# USB.net
KiCad netlist of a schematic drawn in Altium Designer
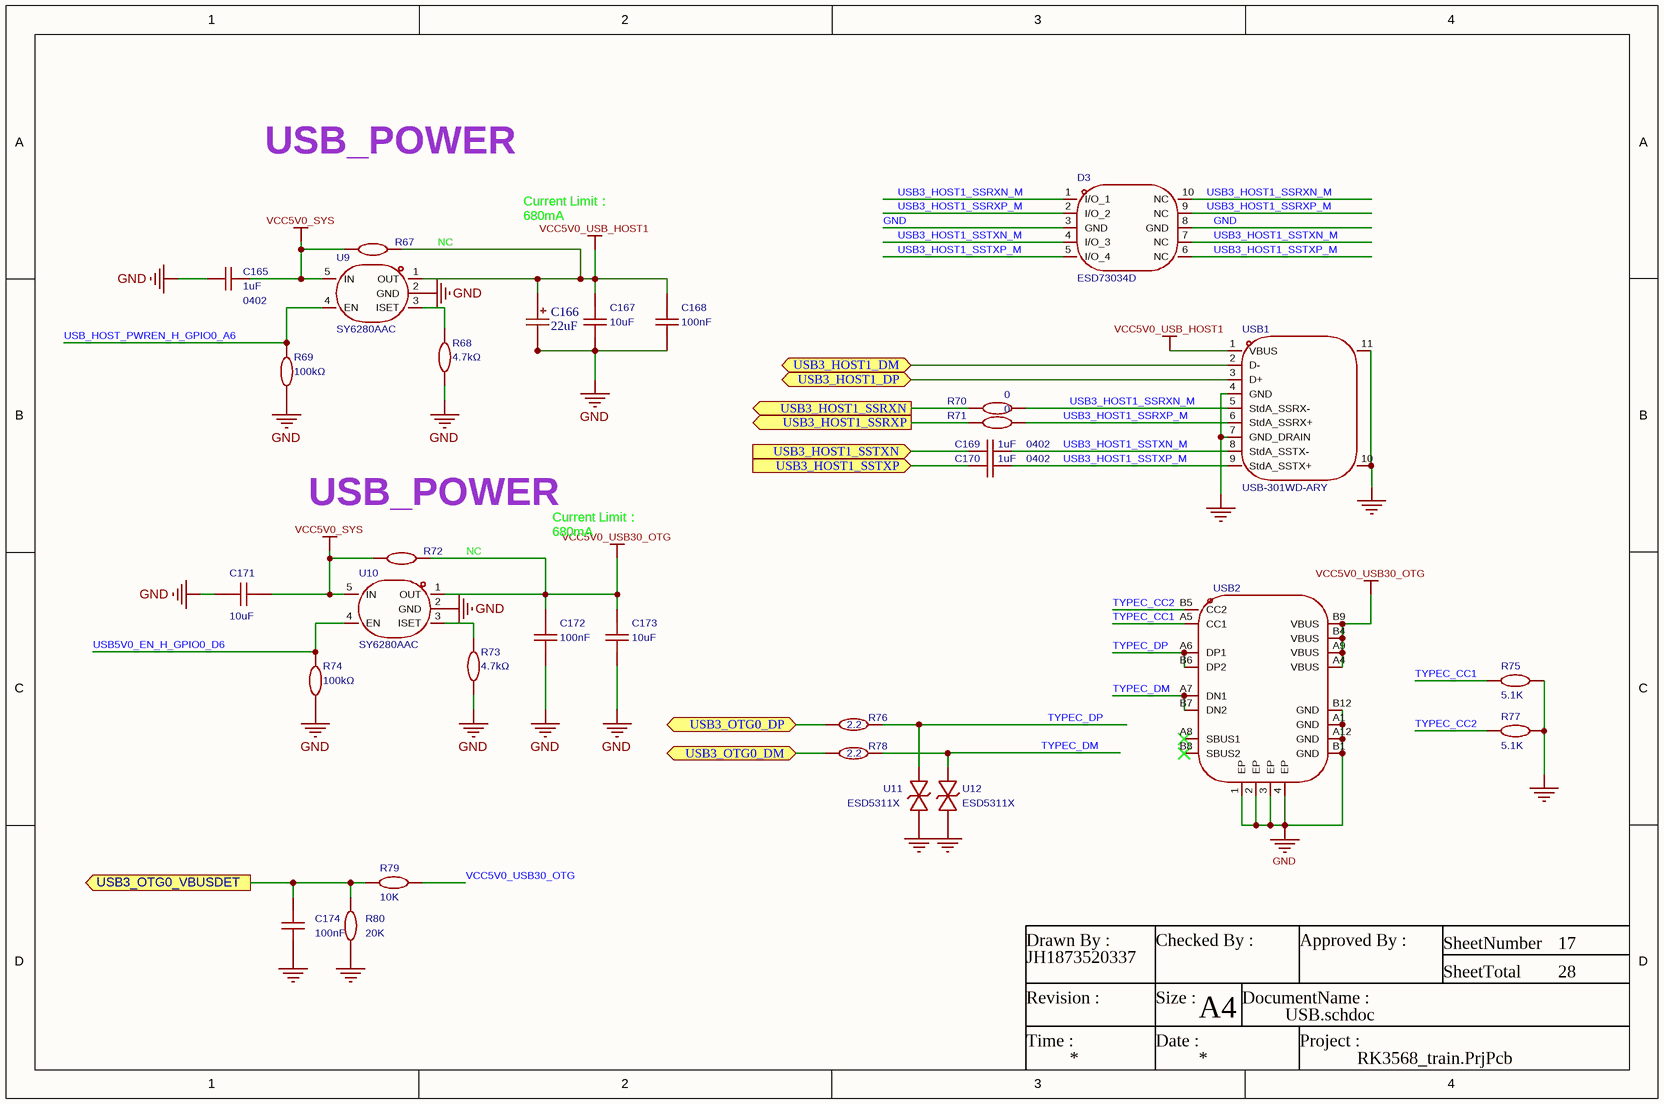
[diagram p0: USB.schdoc]

(export (version "E")
  (design (tool "Eeschema 10.0.6"))
  (components
    (comp (ref "C165")
      (value "1uF")
      (footprint "MYC0402")
      (description "容值:1uF;精度:±10%;额定电压:10V;材质(温度系数):X5R;")
      (fields
        (field (name "SUPPLIER FOOTPRINT") "0402")
        (field (name "MANUFACTURER") "SAMSUNG(三星)")
        (field (name "MANUFACTURER PART") "CL05A105KP5NNNC")
      )
      (libsource (lib "altium-import") (part "root_0_CL05A105KP5NNNC_"))
    )
    (comp (ref "C166")
      (value "22uF")
      (footprint "CASE-B_3528")
      (description "容值:22uF;精度:±10%;额定电压:16V;等效串联电阻(ESR):2.3Ω@100kHz;")
      (fields (field (name "MANUFACTURER") "Kyocera AVX") (field (name "MANUFACTURER PART") "TAJB226K016RNJ"))
      (libsource (lib "钽电容") (part "TAJB226K016RNJ"))
    )
    (comp (ref "C167")
      (value "10uF")
      (footprint "C0603")
      (description "容值:10uF;精度:±10%;额定电压:10V;材质(温度系数):X5R;")
      (fields (field (name "MANUFACTURER") "SAMSUNG(三星)") (field (name "MANUFACTURERPART") "CL10A106KP8NNNC"))
      (libsource (lib "altium-import") (part "root_1_CL10A106KP8NNNC_"))
    )
    (comp (ref "C168")
      (value "100nF")
      (footprint "C0603")
      (description "容值:100nF;精度:±10%;额定电压:50V;材质(温度系数):X7R;")
      (fields (field (name "MANUFACTURER") "YAGEO(国巨)") (field (name "MANUFACTURERPART") "CC0603KRX7R9BB104"))
      (libsource (lib "altium-import") (part "root_1_CC0603KRX7R9BB104_"))
    )
    (comp (ref "C169")
      (value "1uF")
      (footprint "MYC0402")
      (description "容值:1uF;精度:±10%;额定电压:10V;材质(温度系数):X5R;")
      (fields
        (field (name "SUPPLIER FOOTPRINT") "0402")
        (field (name "MANUFACTURER") "SAMSUNG(三星)")
        (field (name "MANUFACTURERPART") "CL05A105KP5NNNC")
      )
      (libsource (lib "altium-import") (part "root_0_CL05A105KP5NNNC_"))
    )
    (comp (ref "C170")
      (value "1uF")
      (footprint "MYC0402")
      (description "容值:1uF;精度:±10%;额定电压:10V;材质(温度系数):X5R;")
      (fields
        (field (name "SUPPLIER FOOTPRINT") "0402")
        (field (name "MANUFACTURER") "SAMSUNG(三星)")
        (field (name "MANUFACTURERPART") "CL05A105KP5NNNC")
      )
      (libsource (lib "altium-import") (part "root_0_CL05A105KP5NNNC_"))
    )
    (comp (ref "C171")
      (value "10uF")
      (footprint "C0603")
      (libsource (lib "altium-import") (part "root_0_CAP_0603_"))
    )
    (comp (ref "C172")
      (value "100nF")
      (footprint "C0603")
      (description "容值:100nF;精度:±10%;额定电压:50V;材质(温度系数):X7R;")
      (fields (field (name "MANUFACTURER") "YAGEO(国巨)") (field (name "MANUFACTURERPART") "CC0603KRX7R9BB104"))
      (libsource (lib "altium-import") (part "root_1_CC0603KRX7R9BB104_"))
    )
    (comp (ref "C173")
      (value "10uF")
      (footprint "C0603")
      (description "容值:10uF;精度:±10%;额定电压:10V;材质(温度系数):X5R;")
      (fields (field (name "MANUFACTURER") "SAMSUNG(三星)") (field (name "MANUFACTURERPART") "CL10A106KP8NNNC"))
      (libsource (lib "altium-import") (part "root_1_CL10A106KP8NNNC_"))
    )
    (comp (ref "C174")
      (value "100nF")
      (footprint "MYC0402")
      (description "容值:1uF;精度:±10%;额定电压:50V;材质(温度系数):X5R;")
      (fields (field (name "MANUFACTURER") "SAMSUNG(三星)") (field (name "MANUFACTURERPART") "CL10A105KB8NNNC"))
      (libsource (lib "altium-import") (part "root_3_CL10A105KB8NNNC_"))
    )
    (comp (ref "D3")
      (value "ESD73034D")
      (footprint "DFN-10_L2.5-W1.0-P0.50-BL-2")
      (description "极性:双向;反向截止电压(Vrwm):3.3V;钳位电压:18V;峰值脉冲电流(Ipp):3A@8/20us;峰值脉冲功率(Ppp):60W@8/20us;击穿电压:8.5V;")
      (fields (field (name "MANUFACTURER") "TECH PUBLIC(台舟)"))
      (libsource (lib "altium-import") (part "root_0_ESD73034D_"))
    )
    (comp (ref "R67")
      (value "NC")
      (footprint "R0805")
      (description "电阻类型:厚膜电阻;阻值:0Ω;精度:±1%;功率:125mW;温度系数:±800ppm/℃;最大工作电压:150V;工作温度范围:-55℃~+155℃;")
      (fields
        (field (name "MANUFACTURER") "UNI-ROYAL(厚声)")
        (field (name "MANUFACTURERPART") "0805W8F0000T5E")
      )
      (libsource (lib "altium-import") (part "root_0_0805W8F0000T5E_"))
    )
    (comp (ref "R68")
      (value "4.7kΩ")
      (footprint "R0402")
      (description "电阻类型:厚膜电阻;阻值:10kΩ;精度:±1%;功率:63mW;温度系数:±100ppm/K;最大工作电压:50V;工作温度范围:-55℃~+155℃;")
      (fields (field (name "MANUFACTURER") "VISHAY(威世)") (field (name "MANUFACTURERPART") "CRCW040210K0FKED"))
      (libsource (lib "altium-import") (part "root_1_CRCW040210K0FKED_"))
    )
    (comp (ref "R69")
      (value "100kΩ")
      (footprint "R0402")
      (description "电阻类型:厚膜电阻;阻值:10kΩ;精度:±1%;功率:63mW;温度系数:±100ppm/K;最大工作电压:50V;工作温度范围:-55℃~+155℃;")
      (fields (field (name "MANUFACTURER") "VISHAY(威世)") (field (name "MANUFACTURERPART") "CRCW040210K0FKED"))
      (libsource (lib "altium-import") (part "root_1_CRCW040210K0FKED_"))
    )
    (comp (ref "R70")
      (value "0")
      (footprint "R0402")
      (libsource (lib "altium-import") (part "root_0_Res_0402_"))
    )
    (comp (ref "R71")
      (value "0")
      (footprint "R0402")
      (libsource (lib "altium-import") (part "root_0_Res_0402_"))
    )
    (comp (ref "R72")
      (value "NC")
      (footprint "R0805")
      (description "电阻类型:厚膜电阻;阻值:0Ω;精度:±1%;功率:125mW;温度系数:±800ppm/℃;最大工作电压:150V;工作温度范围:-55℃~+155℃;")
      (fields
        (field (name "MANUFACTURER") "UNI-ROYAL(厚声)")
        (field (name "MANUFACTURERPART") "0805W8F0000T5E")
      )
      (libsource (lib "altium-import") (part "root_0_0805W8F0000T5E_"))
    )
    (comp (ref "R73")
      (value "4.7kΩ")
      (footprint "R0402")
      (description "电阻类型:厚膜电阻;阻值:10kΩ;精度:±1%;功率:63mW;温度系数:±100ppm/K;最大工作电压:50V;工作温度范围:-55℃~+155℃;")
      (fields (field (name "MANUFACTURER") "VISHAY(威世)") (field (name "MANUFACTURERPART") "CRCW040210K0FKED"))
      (libsource (lib "altium-import") (part "root_1_CRCW040210K0FKED_"))
    )
    (comp (ref "R74")
      (value "100kΩ")
      (footprint "R0402")
      (description "电阻类型:厚膜电阻;阻值:10kΩ;精度:±1%;功率:63mW;温度系数:±100ppm/K;最大工作电压:50V;工作温度范围:-55℃~+155℃;")
      (fields (field (name "MANUFACTURER") "VISHAY(威世)") (field (name "MANUFACTURERPART") "CRCW040210K0FKED"))
      (libsource (lib "altium-import") (part "root_1_CRCW040210K0FKED_"))
    )
    (comp (ref "R75")
      (value "5.1K")
      (footprint "R0402")
      (libsource (lib "altium-import") (part "root_2_Res_0402_"))
    )
    (comp (ref "R76")
      (value "2.2")
      (footprint "R0402")
      (libsource (lib "altium-import") (part "root_0_Res_0402_"))
    )
    (comp (ref "R77")
      (value "5.1K")
      (footprint "R0402")
      (libsource (lib "altium-import") (part "root_2_Res_0402_"))
    )
    (comp (ref "R78")
      (value "2.2")
      (footprint "R0402")
      (libsource (lib "altium-import") (part "root_0_Res_0402_"))
    )
    (comp (ref "R79")
      (value "10K")
      (footprint "R0402")
      (libsource (lib "altium-import") (part "root_0_Res_0402_"))
    )
    (comp (ref "R80")
      (value "20K")
      (footprint "R0402")
      (libsource (lib "altium-import") (part "root_1_Res_0402_"))
    )
    (comp (ref "U9")
      (value "SY6280AAC")
      (footprint "SOT-23-5_L3.0-W1.7-P0.95-LS2.8-BL")
      (description "低能耗配电开关")
      (fields (field (name "MANUFACTURER") "silergy(矽力杰)"))
      (libsource (lib "altium-import") (part "root_3_mirrored_SY6280AAC_C55136_"))
    )
    (comp (ref "U10")
      (value "SY6280AAC")
      (footprint "SOT-23-5_L3.0-W1.7-P0.95-LS2.8-BL")
      (description "低能耗配电开关")
      (fields (field (name "MANUFACTURER") "silergy(矽力杰)"))
      (libsource (lib "altium-import") (part "root_3_mirrored_SY6280AAC_C55136_"))
    )
    (comp (ref "U11")
      (value "ESD5311X")
      (footprint "DFN1006-2L-BI")
      (description "极性:双向;反向截止电压(Vrwm):5V;最大钳位电压:21V;峰值脉冲电流(Ipp):4A;峰值脉冲功率(Ppp):80W;击穿电压:7.5V;")
      (fields (field (name "MANUFACTURER") "TECH PUBLIC(台舟)"))
      (libsource (lib "altium-import") (part "root_3_ESD5311X_C2844730_"))
    )
    (comp (ref "U12")
      (value "ESD5311X")
      (footprint "DFN1006-2L-BI")
      (description "极性:双向;反向截止电压(Vrwm):5V;最大钳位电压:21V;峰值脉冲电流(Ipp):4A;峰值脉冲功率(Ppp):80W;击穿电压:7.5V;")
      (fields (field (name "MANUFACTURER") "TECH PUBLIC(台舟)"))
      (libsource (lib "altium-import") (part "root_3_ESD5311X_C2844730_"))
    )
    (comp (ref "USB1")
      (value "USB-301WD-ARY")
      (footprint "USB-TH_XUNPU_USB-301WD-ARY")
      (description "连接器类型:Type-A;协议标准:USB 3.0;公母:母;安装方式:弯插;触点数量:9P;端口数量:1;额定电流 - 电源:1.8A;工作温度:-55℃~+85℃;")
      (fields (field (name "MANUFACTURER") "XUNPU(讯普)"))
      (libsource (lib "altium-import") (part "root_0_USB-301WD-ARY_"))
    )
    (comp (ref "USB2")
      (value "~")
      (footprint "USB_TYPE-C-16P")
      (libsource (lib "altium-import") (part "root_0_USB_TYPE-C-16P_"))
    )
  )
  (nets
    (net (code "1") (name "/TYPEC_CC1") (class "Default")
      (node (ref "R75") (pin "2") (pinfunction "2_2") (pintype "passive"))
      (node (ref "USB2") (pin "A5") (pinfunction "CC1_A5") (pintype "passive"))
    )
    (net (code "2") (name "/TYPEC_CC2") (class "Default")
      (node (ref "R77") (pin "2") (pinfunction "2_2") (pintype "passive"))
      (node (ref "USB2") (pin "B5") (pinfunction "CC2_B5") (pintype "passive"))
    )
    (net (code "3") (name "/TYPEC_DM") (class "Default")
      (node (ref "R78") (pin "2") (pinfunction "2_2") (pintype "passive"))
      (node (ref "U12") (pin "1") (pinfunction "1_1") (pintype "passive"))
      (node (ref "USB2") (pin "A7") (pinfunction "DN1_A7") (pintype "passive"))
      (node (ref "USB2") (pin "B7") (pinfunction "DN2_B7") (pintype "passive"))
    )
    (net (code "4") (name "/TYPEC_DP") (class "Default")
      (node (ref "R76") (pin "2") (pinfunction "2_2") (pintype "passive"))
      (node (ref "U11") (pin "1") (pinfunction "1_1") (pintype "passive"))
      (node (ref "USB2") (pin "A6") (pinfunction "DP1_A6") (pintype "passive"))
      (node (ref "USB2") (pin "B6") (pinfunction "DP2_B6") (pintype "passive"))
    )
    (net (code "5") (name "/USB3_HOST1_DM") (class "Default")
      (node (ref "USB1") (pin "2") (pinfunction "D-_2") (pintype "passive"))
    )
    (net (code "6") (name "/USB3_HOST1_DP") (class "Default")
      (node (ref "USB1") (pin "3") (pinfunction "D+_3") (pintype "passive"))
    )
    (net (code "7") (name "/USB3_HOST1_SSRXN") (class "Default")
      (node (ref "R70") (pin "1") (pinfunction "1_1") (pintype "passive"))
    )
    (net (code "8") (name "/USB3_HOST1_SSRXN_M") (class "Default")
      (node (ref "D3") (pin "1") (pinfunction "I/O_1_1") (pintype "passive"))
      (node (ref "D3") (pin "10") (pinfunction "NC_10") (pintype "passive"))
      (node (ref "R70") (pin "2") (pinfunction "2_2") (pintype "passive"))
      (node (ref "USB1") (pin "5") (pinfunction "StdA_SSRX-_5") (pintype "passive"))
    )
    (net (code "9") (name "/USB3_HOST1_SSRXP") (class "Default")
      (node (ref "R71") (pin "1") (pinfunction "1_1") (pintype "passive"))
    )
    (net (code "10") (name "/USB3_HOST1_SSRXP_M") (class "Default")
      (node (ref "D3") (pin "2") (pinfunction "I/O_2_2") (pintype "passive"))
      (node (ref "D3") (pin "9") (pinfunction "NC_9") (pintype "passive"))
      (node (ref "R71") (pin "2") (pinfunction "2_2") (pintype "passive"))
      (node (ref "USB1") (pin "6") (pinfunction "StdA_SSRX+_6") (pintype "passive"))
    )
    (net (code "11") (name "/USB3_HOST1_SSTXN") (class "Default")
      (node (ref "C169") (pin "1") (pinfunction "1_1") (pintype "passive"))
    )
    (net (code "12") (name "/USB3_HOST1_SSTXN_M") (class "Default")
      (node (ref "C169") (pin "2") (pinfunction "2_2") (pintype "passive"))
      (node (ref "D3") (pin "4") (pinfunction "I/O_3_4") (pintype "passive"))
      (node (ref "D3") (pin "7") (pinfunction "NC_7") (pintype "passive"))
      (node (ref "USB1") (pin "8") (pinfunction "StdA_SSTX-_8") (pintype "passive"))
    )
    (net (code "13") (name "/USB3_HOST1_SSTXP") (class "Default")
      (node (ref "C170") (pin "1") (pinfunction "1_1") (pintype "passive"))
    )
    (net (code "14") (name "/USB3_HOST1_SSTXP_M") (class "Default")
      (node (ref "C170") (pin "2") (pinfunction "2_2") (pintype "passive"))
      (node (ref "D3") (pin "5") (pinfunction "I/O_4_5") (pintype "passive"))
      (node (ref "D3") (pin "6") (pinfunction "NC_6") (pintype "passive"))
      (node (ref "USB1") (pin "9") (pinfunction "StdA_SSTX+_9") (pintype "passive"))
    )
    (net (code "15") (name "/USB3_OTG0_DM") (class "Default")
      (node (ref "R78") (pin "1") (pinfunction "1_1") (pintype "passive"))
    )
    (net (code "16") (name "/USB3_OTG0_DP") (class "Default")
      (node (ref "R76") (pin "1") (pinfunction "1_1") (pintype "passive"))
    )
    (net (code "17") (name "/USB3_OTG0_VBUSDET") (class "Default")
      (node (ref "C174") (pin "1") (pinfunction "1_1") (pintype "passive"))
      (node (ref "R79") (pin "1") (pinfunction "1_1") (pintype "passive"))
      (node (ref "R80") (pin "2") (pinfunction "2_2") (pintype "passive"))
    )
    (net (code "18") (name "/USB5V0_EN_H_GPIO0_D6") (class "Default")
      (node (ref "R74") (pin "2") (pinfunction "2_2") (pintype "passive"))
      (node (ref "U10") (pin "4") (pinfunction "EN_4") (pintype "passive"))
    )
    (net (code "19") (name "/USB_HOST_PWREN_H_GPIO0_A6") (class "Default")
      (node (ref "R69") (pin "2") (pinfunction "2_2") (pintype "passive"))
      (node (ref "U9") (pin "4") (pinfunction "EN_4") (pintype "passive"))
    )
    (net (code "20") (name "GND") (class "Default")
      (node (ref "C165") (pin "1") (pinfunction "1_1") (pintype "passive"))
      (node (ref "C166") (pin "2") (pinfunction "2_2") (pintype "passive"))
      (node (ref "C167") (pin "1") (pinfunction "1_1") (pintype "passive"))
      (node (ref "C168") (pin "1") (pinfunction "1_1") (pintype "passive"))
      (node (ref "C171") (pin "1") (pinfunction "1_1") (pintype "passive"))
      (node (ref "C172") (pin "1") (pinfunction "1_1") (pintype "passive"))
      (node (ref "C173") (pin "1") (pinfunction "1_1") (pintype "passive"))
      (node (ref "C174") (pin "2") (pinfunction "2_2") (pintype "passive"))
      (node (ref "D3") (pin "3") (pinfunction "GND_3") (pintype "passive"))
      (node (ref "D3") (pin "8") (pinfunction "GND_8") (pintype "passive"))
      (node (ref "R68") (pin "1") (pinfunction "1_1") (pintype "passive"))
      (node (ref "R69") (pin "1") (pinfunction "1_1") (pintype "passive"))
      (node (ref "R73") (pin "1") (pinfunction "1_1") (pintype "passive"))
      (node (ref "R74") (pin "1") (pinfunction "1_1") (pintype "passive"))
      (node (ref "R75") (pin "1") (pinfunction "1_1") (pintype "passive"))
      (node (ref "R77") (pin "1") (pinfunction "1_1") (pintype "passive"))
      (node (ref "R80") (pin "1") (pinfunction "1_1") (pintype "passive"))
      (node (ref "U10") (pin "2") (pinfunction "GND_2") (pintype "passive"))
      (node (ref "U11") (pin "2") (pinfunction "2_2") (pintype "passive"))
      (node (ref "U12") (pin "2") (pinfunction "2_2") (pintype "passive"))
      (node (ref "U9") (pin "2") (pinfunction "GND_2") (pintype "passive"))
      (node (ref "USB1") (pin "10") (pinfunction "SHIELD_10") (pintype "passive"))
      (node (ref "USB1") (pin "11") (pinfunction "SHIELD_11") (pintype "passive"))
      (node (ref "USB1") (pin "4") (pinfunction "GND_4") (pintype "passive"))
      (node (ref "USB1") (pin "7") (pinfunction "GND_DRAIN_7") (pintype "passive"))
      (node (ref "USB2") (pin "1") (pinfunction "EP_1") (pintype "passive"))
      (node (ref "USB2") (pin "2") (pinfunction "EP_2") (pintype "passive"))
      (node (ref "USB2") (pin "3") (pinfunction "EP_3") (pintype "passive"))
      (node (ref "USB2") (pin "4") (pinfunction "EP_4") (pintype "passive"))
      (node (ref "USB2") (pin "A1") (pinfunction "GND_A1") (pintype "passive"))
      (node (ref "USB2") (pin "A12") (pinfunction "GND_A12") (pintype "passive"))
      (node (ref "USB2") (pin "B1") (pinfunction "GND_B1") (pintype "passive"))
      (node (ref "USB2") (pin "B12") (pinfunction "GND_B12") (pintype "passive"))
    )
    (net (code "21") (name "Net-(U9-ISET)") (class "Default")
      (node (ref "R68") (pin "2") (pinfunction "2_2") (pintype "passive"))
      (node (ref "U9") (pin "3") (pinfunction "ISET_3") (pintype "passive"))
    )
    (net (code "22") (name "Net-(U10-ISET)") (class "Default")
      (node (ref "R73") (pin "2") (pinfunction "2_2") (pintype "passive"))
      (node (ref "U10") (pin "3") (pinfunction "ISET_3") (pintype "passive"))
    )
    (net (code "23") (name "VCC5V0_SYS") (class "Default")
      (node (ref "C165") (pin "2") (pinfunction "2_2") (pintype "passive"))
      (node (ref "C171") (pin "2") (pinfunction "2_2") (pintype "passive"))
      (node (ref "R67") (pin "1") (pinfunction "1_1") (pintype "passive"))
      (node (ref "R72") (pin "1") (pinfunction "1_1") (pintype "passive"))
      (node (ref "U10") (pin "5") (pinfunction "IN_5") (pintype "passive"))
      (node (ref "U9") (pin "5") (pinfunction "IN_5") (pintype "passive"))
    )
    (net (code "24") (name "VCC5V0_USB30_OTG") (class "Default")
      (node (ref "C172") (pin "2") (pinfunction "2_2") (pintype "passive"))
      (node (ref "C173") (pin "2") (pinfunction "2_2") (pintype "passive"))
      (node (ref "R72") (pin "2") (pinfunction "2_2") (pintype "passive"))
      (node (ref "R79") (pin "2") (pinfunction "2_2") (pintype "passive"))
      (node (ref "U10") (pin "1") (pinfunction "OUT_1") (pintype "passive"))
      (node (ref "USB2") (pin "A4") (pinfunction "VBUS_A4") (pintype "passive"))
      (node (ref "USB2") (pin "A9") (pinfunction "VBUS_A9") (pintype "passive"))
      (node (ref "USB2") (pin "B4") (pinfunction "VBUS_B4") (pintype "passive"))
      (node (ref "USB2") (pin "B9") (pinfunction "VBUS_B9") (pintype "passive"))
    )
    (net (code "25") (name "VCC5V0_USB_HOST1") (class "Default")
      (node (ref "C166") (pin "1") (pinfunction "1_1") (pintype "passive"))
      (node (ref "C167") (pin "2") (pinfunction "2_2") (pintype "passive"))
      (node (ref "C168") (pin "2") (pinfunction "2_2") (pintype "passive"))
      (node (ref "R67") (pin "2") (pinfunction "2_2") (pintype "passive"))
      (node (ref "U9") (pin "1") (pinfunction "OUT_1") (pintype "passive"))
      (node (ref "USB1") (pin "1") (pinfunction "VBUS_1") (pintype "passive"))
    )
    (net (code "26") (name "unconnected-(USB2-SBUS1-PadA8)") (class "Default")
      (node (ref "USB2") (pin "A8") (pinfunction "SBUS1_A8") (pintype "passive+no_connect"))
    )
    (net (code "27") (name "unconnected-(USB2-SBUS2-PadB8)") (class "Default")
      (node (ref "USB2") (pin "B8") (pinfunction "SBUS2_B8") (pintype "passive+no_connect"))
    )
  )
)
